# TSOC_PSoC4L.net
KiCad netlist of a schematic drawn in EAGLE
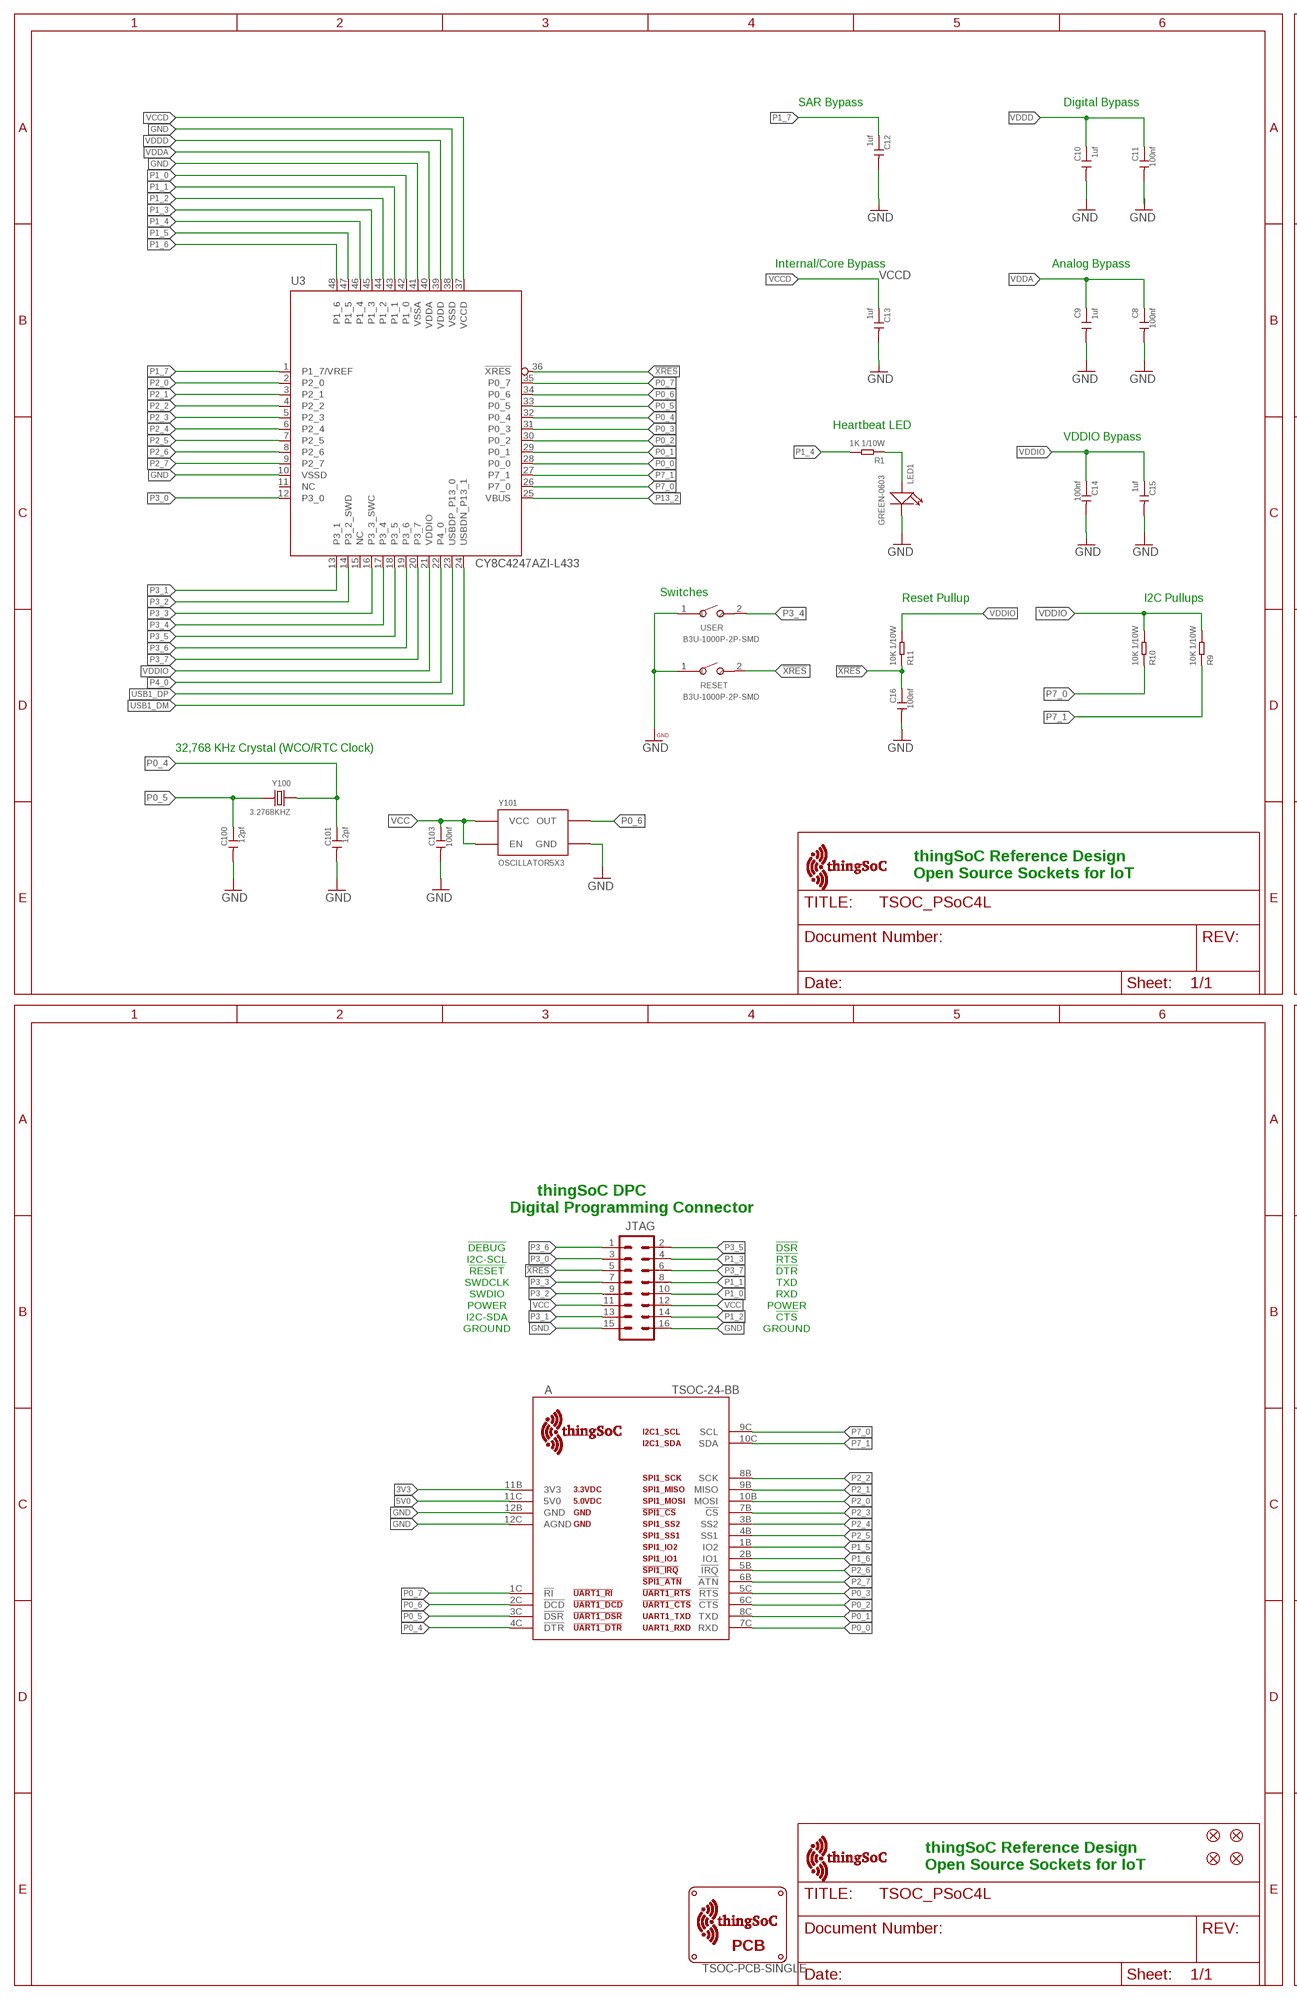
[diagram p0: schematic, sheet 1, part 1 of 2]
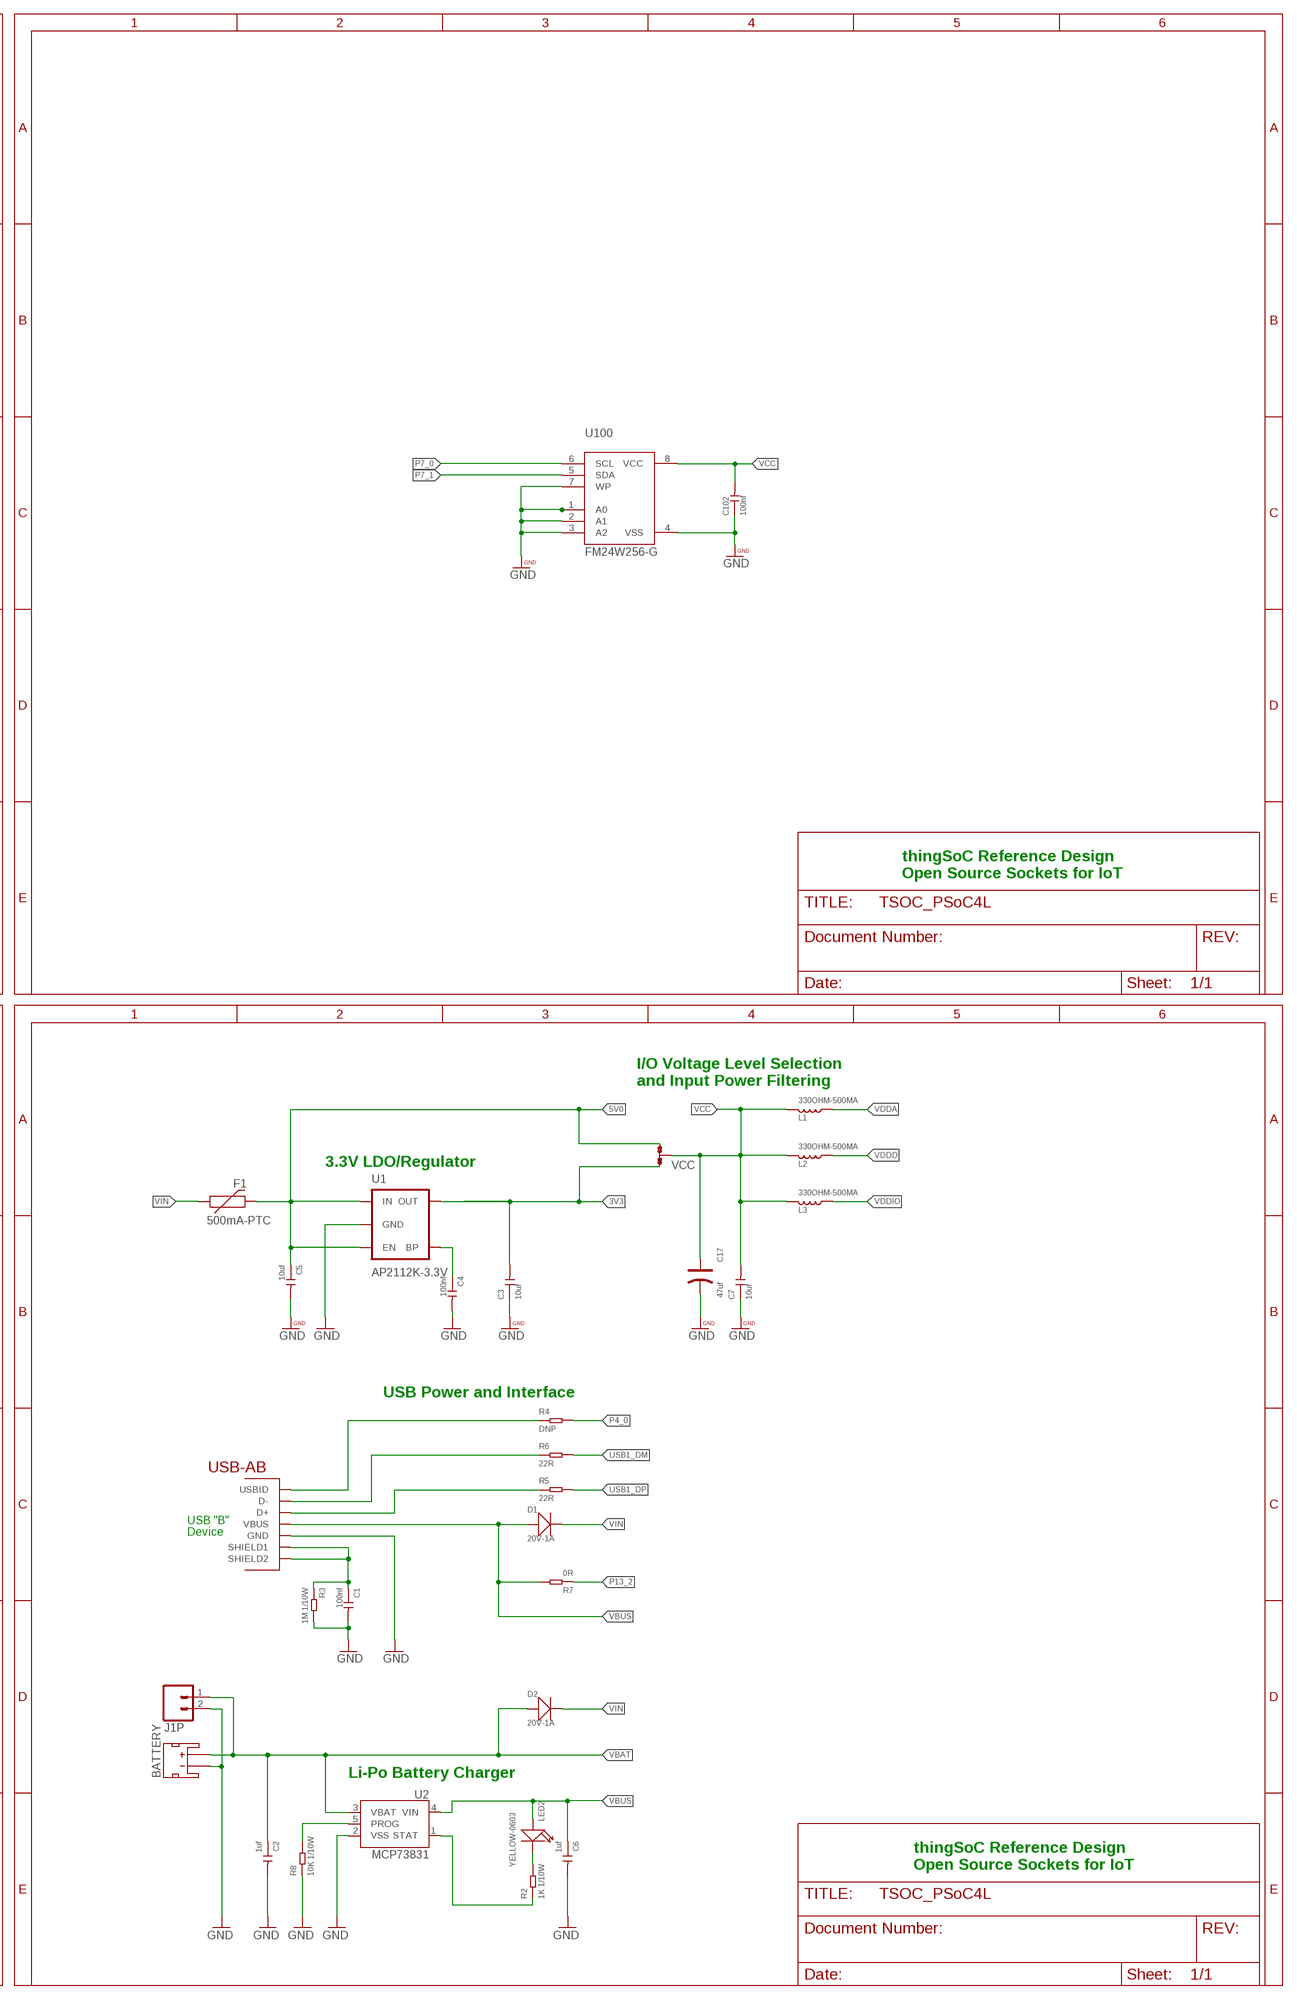
[diagram p1: schematic, sheet 1, part 2 of 2]

(export (version "E")
  (design (tool "Eeschema 10.0.6"))
  (components
    (comp (ref "A")
      (value "TSOC-24-BB")
      (footprint "eagle-import:TSOC-BB-S24")
      (libsource (lib "eagle-import") (part "TSOC-24-BB"))
    )
    (comp (ref "BATTERY")
      (value "JST_2MM_MALE")
      (footprint "eagle-import:JST-2-SMD")
      (libsource (lib "eagle-import") (part "JST_2MM_MALE"))
    )
    (comp (ref "C1")
      (value "100nf")
      (footprint "eagle-import:C0603")
      (fields (field (name "MPN") "CC0603KRX7R9BB104"))
      (libsource (lib "eagle-import") (part "CERAMIC-100NF-50V-10%-X7R(0603)"))
    )
    (comp (ref "C2")
      (value "1uf")
      (footprint "eagle-import:C0603")
      (fields (field (name "MPN") "CC0603KRX7R8BB105"))
      (libsource (lib "eagle-import") (part "CERAMIC-1UF-25V-10%-X7R(0603)"))
    )
    (comp (ref "C3")
      (value "10uf")
      (footprint "eagle-import:C0603")
      (fields (field (name "MPN") "CC0603KRX5R6BB106"))
      (libsource (lib "eagle-import") (part "CERAMIC-10UF-10V-10%-X5R(0603)"))
    )
    (comp (ref "C4")
      (value "100nf")
      (footprint "eagle-import:C0603")
      (fields (field (name "MPN") "CC0603KRX7R9BB104"))
      (libsource (lib "eagle-import") (part "CERAMIC-100NF-50V-10%-X7R(0603)"))
    )
    (comp (ref "C5")
      (value "10uf")
      (footprint "eagle-import:C0603")
      (fields (field (name "MPN") "CC0603KRX5R6BB106"))
      (libsource (lib "eagle-import") (part "CERAMIC-10UF-10V-10%-X5R(0603)"))
    )
    (comp (ref "C6")
      (value "1uf")
      (footprint "eagle-import:C0603")
      (fields (field (name "MPN") "CC0603KRX7R8BB105"))
      (libsource (lib "eagle-import") (part "CERAMIC-1UF-25V-10%-X7R(0603)"))
    )
    (comp (ref "C7")
      (value "10uf")
      (footprint "eagle-import:C0603")
      (fields (field (name "MPN") "CC0603KRX5R6BB106"))
      (libsource (lib "eagle-import") (part "CERAMIC-10UF-10V-10%-X5R(0603)"))
    )
    (comp (ref "C8")
      (value "100nf")
      (footprint "eagle-import:C0603")
      (fields (field (name "MPN") "CC0603KRX7R9BB104"))
      (libsource (lib "eagle-import") (part "CERAMIC-100NF-50V-10%-X7R(0603)"))
    )
    (comp (ref "C9")
      (value "1uf")
      (footprint "eagle-import:C0603")
      (fields (field (name "MPN") "CC0603KRX7R8BB105"))
      (libsource (lib "eagle-import") (part "CERAMIC-1UF-25V-10%-X7R(0603)"))
    )
    (comp (ref "C10")
      (value "1uf")
      (footprint "eagle-import:C0603")
      (fields (field (name "MPN") "CC0603KRX7R8BB105"))
      (libsource (lib "eagle-import") (part "CERAMIC-1UF-25V-10%-X7R(0603)"))
    )
    (comp (ref "C11")
      (value "100nf")
      (footprint "eagle-import:C0603")
      (fields (field (name "MPN") "CC0603KRX7R9BB104"))
      (libsource (lib "eagle-import") (part "CERAMIC-100NF-50V-10%-X7R(0603)"))
    )
    (comp (ref "C12")
      (value "1uf")
      (footprint "eagle-import:C0603")
      (fields (field (name "MPN") "CC0603KRX7R8BB105"))
      (libsource (lib "eagle-import") (part "CERAMIC-1UF-25V-10%-X7R(0603)"))
    )
    (comp (ref "C13")
      (value "1uf")
      (footprint "eagle-import:C0603")
      (fields (field (name "MPN") "CC0603KRX7R8BB105"))
      (libsource (lib "eagle-import") (part "CERAMIC-1UF-25V-10%-X7R(0603)"))
    )
    (comp (ref "C14")
      (value "100nf")
      (footprint "eagle-import:C0603")
      (fields (field (name "MPN") "CC0603KRX7R9BB104"))
      (libsource (lib "eagle-import") (part "CERAMIC-100NF-50V-10%-X7R(0603)"))
    )
    (comp (ref "C15")
      (value "1uf")
      (footprint "eagle-import:C0603")
      (fields (field (name "MPN") "CC0603KRX7R8BB105"))
      (libsource (lib "eagle-import") (part "CERAMIC-1UF-25V-10%-X7R(0603)"))
    )
    (comp (ref "C16")
      (value "100nf")
      (footprint "eagle-import:C0603")
      (fields (field (name "MPN") "CC0603KRX7R9BB104"))
      (libsource (lib "eagle-import") (part "CERAMIC-100NF-50V-10%-X7R(0603)"))
    )
    (comp (ref "C17")
      (value "47uf")
      (footprint "eagle-import:AVX-A")
      (fields (field (name "MPN") "TAJA476*006#NJ"))
      (libsource (lib "eagle-import") (part "TANTALUM-SMD-47UF-6.3V(AVX-A)"))
    )
    (comp (ref "C100")
      (value "12pf")
      (footprint "eagle-import:C0603")
      (fields (field (name "MPN") "CC0603JRNPO9BN120"))
      (libsource (lib "eagle-import") (part "CERAMIC-12PF-50V-5%-NPO(0603)"))
    )
    (comp (ref "C101")
      (value "12pf")
      (footprint "eagle-import:C0603")
      (fields (field (name "MPN") "CC0603JRNPO9BN120"))
      (libsource (lib "eagle-import") (part "CERAMIC-12PF-50V-5%-NPO(0603)"))
    )
    (comp (ref "C102")
      (value "100nf")
      (footprint "eagle-import:C0603")
      (fields (field (name "MPN") "CC0603KRX7R9BB104"))
      (libsource (lib "eagle-import") (part "CERAMIC-100NF-50V-10%-X7R(0603)"))
    )
    (comp (ref "C103")
      (value "100nf")
      (footprint "eagle-import:C0603")
      (fields (field (name "MPN") "CC0603KRX7R9BB104"))
      (libsource (lib "eagle-import") (part "CERAMIC-100NF-50V-10%-X7R(0603)"))
    )
    (comp (ref "D1")
      (value "20V-1A")
      (footprint "eagle-import:SOD-123")
      (fields (field (name "MPN") "B5819W"))
      (libsource (lib "eagle-import") (part "SMD-DIODE-SCHOTTKY-20V-1A(SOD-123)"))
    )
    (comp (ref "D2")
      (value "20V-1A")
      (footprint "eagle-import:SOD-123")
      (fields (field (name "MPN") "B5819W"))
      (libsource (lib "eagle-import") (part "SMD-DIODE-SCHOTTKY-20V-1A(SOD-123)"))
    )
    (comp (ref "F1")
      (value "500mA-PTC")
      (footprint "eagle-import:PTC-1206")
      (libsource (lib "eagle-import") (part "PTCSMD"))
    )
    (comp (ref "FID1")
      (value "FIDUCIALUFIDUCIAL")
      (footprint "eagle-import:MICRO-FIDUCIAL")
      (libsource (lib "eagle-import") (part "FIDUCIALUFIDUCIAL"))
    )
    (comp (ref "FID2")
      (value "FIDUCIALUFIDUCIAL")
      (footprint "eagle-import:MICRO-FIDUCIAL")
      (libsource (lib "eagle-import") (part "FIDUCIALUFIDUCIAL"))
    )
    (comp (ref "FID3")
      (value "FIDUCIALUFIDUCIAL")
      (footprint "eagle-import:MICRO-FIDUCIAL")
      (libsource (lib "eagle-import") (part "FIDUCIALUFIDUCIAL"))
    )
    (comp (ref "FID4")
      (value "FIDUCIALUFIDUCIAL")
      (footprint "eagle-import:MICRO-FIDUCIAL")
      (libsource (lib "eagle-import") (part "FIDUCIALUFIDUCIAL"))
    )
    (comp (ref "J1P")
      (value "M02-JST-2-PTH-NO_SILK")
      (footprint "eagle-import:JST-2-PTH-NS")
      (libsource (lib "eagle-import") (part "M02-JST-2-PTH-NO_SILK"))
    )
    (comp (ref "JTAG")
      (value "M08X2")
      (footprint "eagle-import:2X8")
      (libsource (lib "eagle-import") (part "M08X2"))
    )
    (comp (ref "L1")
      (value "330OHM-500MA")
      (footprint "eagle-import:L0603")
      (fields (field (name "MPN") "BLM18AG121SN1D"))
      (libsource (lib "eagle-import") (part "SMD-FERRITE-CHIP-120-OHM-500MA(0603)"))
    )
    (comp (ref "L2")
      (value "330OHM-500MA")
      (footprint "eagle-import:L0603")
      (fields (field (name "MPN") "BLM18AG121SN1D"))
      (libsource (lib "eagle-import") (part "SMD-FERRITE-CHIP-120-OHM-500MA(0603)"))
    )
    (comp (ref "L3")
      (value "330OHM-500MA")
      (footprint "eagle-import:L0603")
      (fields (field (name "MPN") "BLM18AG121SN1D"))
      (libsource (lib "eagle-import") (part "SMD-FERRITE-CHIP-120-OHM-500MA(0603)"))
    )
    (comp (ref "LED1")
      (value "GREEN-0603")
      (footprint "eagle-import:LED-0603")
      (fields (field (name "MPN") "19-217-G7C-AN1P2-3T"))
      (libsource (lib "eagle-import") (part "SMD-LED-CLEAR-GREEN(0603)"))
    )
    (comp (ref "LED2")
      (value "YELLOW-0603")
      (footprint "eagle-import:LED-0603")
      (fields (field (name "MPN") "19-217-Y5C-AM1N1VY-3T"))
      (libsource (lib "eagle-import") (part "SMD-LED-CLEAR-YELLOW(0603)"))
    )
    (comp (ref "R1")
      (value "1K 1/10W")
      (footprint "eagle-import:R0603")
      (fields (field (name "MPN") "RC0603JR-071KL"))
      (libsource (lib "eagle-import") (part "SMD-RES-1K-5%-1/10W(0603)"))
    )
    (comp (ref "R2")
      (value "1K 1/10W")
      (footprint "eagle-import:R0603")
      (fields (field (name "MPN") "RC0603JR-071KL"))
      (libsource (lib "eagle-import") (part "SMD-RES-1K-5%-1/10W(0603)"))
    )
    (comp (ref "R3")
      (value "1M 1/10W")
      (footprint "eagle-import:R0603")
      (fields (field (name "MPN") "RC0603JR-071ML"))
      (libsource (lib "eagle-import") (part "SMD-RES-1M-5%-1/10W(0603)"))
    )
    (comp (ref "R4")
      (value "DNP")
      (footprint "eagle-import:R0603")
      (fields (field (name "MPN") "RC0603JR-0722RL"))
      (libsource (lib "eagle-import") (part "SMD-RES-22R-5%-1/10W(0603)"))
    )
    (comp (ref "R5")
      (value "22R")
      (footprint "eagle-import:R0603")
      (fields (field (name "MPN") "RC0603JR-0722RL"))
      (libsource (lib "eagle-import") (part "SMD-RES-22R-5%-1/10W(0603)"))
    )
    (comp (ref "R6")
      (value "22R")
      (footprint "eagle-import:R0603")
      (fields (field (name "MPN") "RC0603JR-0722RL"))
      (libsource (lib "eagle-import") (part "SMD-RES-22R-5%-1/10W(0603)"))
    )
    (comp (ref "R7")
      (value "0R")
      (footprint "eagle-import:R0603")
      (fields (field (name "MPN") "RC0603JR-070RL"))
      (libsource (lib "eagle-import") (part "SMD-RES-0R-5%-1/10W(0603)"))
    )
    (comp (ref "R8")
      (value "10K 1/10W")
      (footprint "eagle-import:R0603")
      (fields (field (name "MPN") "RC0603JR-0710KL"))
      (libsource (lib "eagle-import") (part "SMD-RES-10K-5%-1/10W(0603)"))
    )
    (comp (ref "R9")
      (value "10K 1/10W")
      (footprint "eagle-import:R0603")
      (fields (field (name "MPN") "RC0603JR-0710KL"))
      (libsource (lib "eagle-import") (part "SMD-RES-10K-5%-1/10W(0603)"))
    )
    (comp (ref "R10")
      (value "10K 1/10W")
      (footprint "eagle-import:R0603")
      (fields (field (name "MPN") "RC0603JR-0710KL"))
      (libsource (lib "eagle-import") (part "SMD-RES-10K-5%-1/10W(0603)"))
    )
    (comp (ref "R11")
      (value "10K 1/10W")
      (footprint "eagle-import:R0603")
      (fields (field (name "MPN") "RC0603JR-0710KL"))
      (libsource (lib "eagle-import") (part "SMD-RES-10K-5%-1/10W(0603)"))
    )
    (comp (ref "RESET")
      (value "B3U-1000P-2P-SMD")
      (footprint "eagle-import:SW2-2.6-3.0X2.5X1.2+0.4MM")
      (libsource (lib "eagle-import") (part "SMD-BUTTON(2P-3.0X2.5X1.2+0.4MM)-B3U-1000P-2P-SMD"))
    )
    (comp (ref "U$1")
      (value "TSOC-PCB-SINGLE")
      (footprint "eagle-import:TSOC-BB-BRD-DIM")
      (libsource (lib "eagle-import") (part "TSOC-PCB-SINGLE"))
    )
    (comp (ref "U$100")
      (value "TSOC-LOGO-LRG")
      (footprint "eagle-import:TSOC-LOGO-LRG")
      (libsource (lib "eagle-import") (part "TSOC-LOGO-LRG"))
    )
    (comp (ref "U$101")
      (value "TSOC-LOGO-SMALL")
      (footprint "eagle-import:TSOC-LOGO-SML")
      (libsource (lib "eagle-import") (part "TSOC-LOGO-SMALL"))
    )
    (comp (ref "U1")
      (value "AP2112K-3.3V")
      (footprint "eagle-import:SOT23-5")
      (libsource (lib "eagle-import") (part "V_REG_LDOSMD"))
    )
    (comp (ref "U2")
      (value "MCP73831")
      (footprint "eagle-import:SOT23-5")
      (libsource (lib "eagle-import") (part "MCP73831"))
    )
    (comp (ref "U3")
      (value "CY8C4247AZI-L433")
      (footprint "eagle-import:TQFP-7X7-48")
      (libsource (lib "eagle-import") (part "CY8C4247AZI-L433"))
    )
    (comp (ref "U100")
      (value "FM24W256-G")
      (footprint "eagle-import:SO08")
      (libsource (lib "eagle-import") (part "FM24W256-G"))
    )
    (comp (ref "USB")
      (value "USB_AB")
      (footprint "eagle-import:USB-AB-MICRO-SMD")
      (libsource (lib "eagle-import") (part "USB_AB"))
    )
    (comp (ref "USER")
      (value "B3U-1000P-2P-SMD")
      (footprint "eagle-import:SW2-2.6-3.0X2.5X1.2+0.4MM")
      (libsource (lib "eagle-import") (part "SMD-BUTTON(2P-3.0X2.5X1.2+0.4MM)-B3U-1000P-2P-SMD"))
    )
    (comp (ref "VCC")
      (value "JMP-3-1_2")
      (footprint "eagle-import:JMP-3-1_2")
      (libsource (lib "eagle-import") (part "JMP-3-1_2"))
    )
    (comp (ref "Y100")
      (value "3.2768KHZ")
      (footprint "eagle-import:X2-SMD-L2.0X1.2X0.55MM")
      (fields (field (name "MPN") "FC-12M"))
      (libsource (lib "eagle-import") (part "SMD-CRYSTAL-32.768KHZ-12.5PF-20PPM-90K(2P-L2.0X1.2MM)"))
    )
    (comp (ref "Y101")
      (value "OSCILLATOR5X3")
      (footprint "eagle-import:CRYSTAL-SMD-5X3")
      (libsource (lib "eagle-import") (part "OSCILLATOR5X3"))
    )
  )
  (nets
    (net (code "1") (name "/~{XRES}") (class "Default")
      (node (ref "C16") (pin "1") (pinfunction "1_1") (pintype "passive"))
      (node (ref "JTAG") (pin "5") (pinfunction "5_5") (pintype "passive"))
      (node (ref "R11") (pin "1") (pinfunction "1_1") (pintype "passive"))
      (node (ref "RESET") (pin "2") (pinfunction "2_2") (pintype "bidirectional"))
      (node (ref "U3") (pin "36") (pinfunction "~{XRES}_36") (pintype "bidirectional"))
    )
    (net (code "2") (name "3V3") (class "Default")
      (node (ref "A") (pin "11B") (pinfunction "3V3_11B") (pintype "bidirectional"))
      (node (ref "C3") (pin "2") (pinfunction "2_2") (pintype "passive"))
      (node (ref "U1") (pin "5") (pinfunction "OUT_5") (pintype "passive"))
      (node (ref "VCC") (pin "1") (pinfunction "1_1") (pintype "passive"))
    )
    (net (code "3") (name "5V0") (class "Default")
      (node (ref "A") (pin "11C") (pinfunction "5V0_11C") (pintype "bidirectional"))
      (node (ref "C5") (pin "1") (pinfunction "1_1") (pintype "passive"))
      (node (ref "F1") (pin "2") (pinfunction "2_2") (pintype "bidirectional"))
      (node (ref "U1") (pin "1") (pinfunction "IN_1") (pintype "input"))
      (node (ref "U1") (pin "3") (pinfunction "EN_3") (pintype "input"))
      (node (ref "VCC") (pin "3") (pinfunction "3_3") (pintype "passive"))
    )
    (net (code "4") (name "GND") (class "Default")
      (node (ref "A") (pin "12B") (pinfunction "GND_12B") (pintype "bidirectional"))
      (node (ref "A") (pin "12C") (pinfunction "AGND_12C") (pintype "bidirectional"))
      (node (ref "BATTERY") (pin "1") (pinfunction "-_1") (pintype "bidirectional"))
      (node (ref "C1") (pin "2") (pinfunction "2_2") (pintype "passive"))
      (node (ref "C10") (pin "2") (pinfunction "2_2") (pintype "passive"))
      (node (ref "C100") (pin "2") (pinfunction "2_2") (pintype "passive"))
      (node (ref "C101") (pin "2") (pinfunction "2_2") (pintype "passive"))
      (node (ref "C102") (pin "1") (pinfunction "1_1") (pintype "passive"))
      (node (ref "C103") (pin "2") (pinfunction "2_2") (pintype "passive"))
      (node (ref "C11") (pin "2") (pinfunction "2_2") (pintype "passive"))
      (node (ref "C12") (pin "2") (pinfunction "2_2") (pintype "passive"))
      (node (ref "C13") (pin "2") (pinfunction "2_2") (pintype "passive"))
      (node (ref "C14") (pin "2") (pinfunction "2_2") (pintype "passive"))
      (node (ref "C15") (pin "2") (pinfunction "2_2") (pintype "passive"))
      (node (ref "C16") (pin "2") (pinfunction "2_2") (pintype "passive"))
      (node (ref "C17") (pin "-") (pinfunction "-_-") (pintype "passive"))
      (node (ref "C2") (pin "2") (pinfunction "2_2") (pintype "passive"))
      (node (ref "C3") (pin "1") (pinfunction "1_1") (pintype "passive"))
      (node (ref "C4") (pin "2") (pinfunction "2_2") (pintype "passive"))
      (node (ref "C5") (pin "2") (pinfunction "2_2") (pintype "passive"))
      (node (ref "C6") (pin "2") (pinfunction "2_2") (pintype "passive"))
      (node (ref "C7") (pin "1") (pinfunction "1_1") (pintype "passive"))
      (node (ref "C8") (pin "2") (pinfunction "2_2") (pintype "passive"))
      (node (ref "C9") (pin "2") (pinfunction "2_2") (pintype "passive"))
      (node (ref "J1P") (pin "2") (pinfunction "2_2") (pintype "passive"))
      (node (ref "JTAG") (pin "15") (pinfunction "15_15") (pintype "passive"))
      (node (ref "JTAG") (pin "16") (pinfunction "16_16") (pintype "passive"))
      (node (ref "LED1") (pin "-") (pinfunction "-_-") (pintype "passive"))
      (node (ref "R3") (pin "2") (pinfunction "2_2") (pintype "passive"))
      (node (ref "R8") (pin "1") (pinfunction "1_1") (pintype "passive"))
      (node (ref "RESET") (pin "1") (pinfunction "1_1") (pintype "bidirectional"))
      (node (ref "U1") (pin "2") (pinfunction "GND_2") (pintype "input"))
      (node (ref "U100") (pin "1") (pinfunction "A0_1") (pintype "bidirectional"))
      (node (ref "U100") (pin "2") (pinfunction "A1_2") (pintype "bidirectional"))
      (node (ref "U100") (pin "3") (pinfunction "A2_3") (pintype "bidirectional"))
      (node (ref "U100") (pin "4") (pinfunction "VSS_4") (pintype "power_in"))
      (node (ref "U100") (pin "7") (pinfunction "WP_7") (pintype "bidirectional"))
      (node (ref "U2") (pin "2") (pinfunction "VSS_2") (pintype "power_in"))
      (node (ref "U3") (pin "10") (pinfunction "VSSD_10") (pintype "bidirectional"))
      (node (ref "U3") (pin "38") (pinfunction "VSSD_38") (pintype "bidirectional"))
      (node (ref "U3") (pin "41") (pinfunction "VSSA_41") (pintype "bidirectional"))
      (node (ref "USB") (pin "GND") (pinfunction "GND_GND") (pintype "bidirectional"))
      (node (ref "USER") (pin "1") (pinfunction "1_1") (pintype "bidirectional"))
      (node (ref "Y101") (pin "2") (pinfunction "GND_2") (pintype "bidirectional"))
    )
    (net (code "5") (name "Net-(C1-Pad1)") (class "Default")
      (node (ref "C1") (pin "1") (pinfunction "1_1") (pintype "passive"))
      (node (ref "R3") (pin "1") (pinfunction "1_1") (pintype "passive"))
      (node (ref "USB") (pin "SHIELD1") (pinfunction "SHIELD1_SHIELD1") (pintype "bidirectional"))
      (node (ref "USB") (pin "SHIELD2") (pinfunction "SHIELD2_SHIELD2") (pintype "bidirectional"))
    )
    (net (code "6") (name "Net-(LED1-Pad+)") (class "Default")
      (node (ref "LED1") (pin "+") (pinfunction "+_+") (pintype "passive"))
      (node (ref "R1") (pin "1") (pinfunction "1_1") (pintype "passive"))
    )
    (net (code "7") (name "Net-(LED2-Pad-)") (class "Default")
      (node (ref "LED2") (pin "-") (pinfunction "-_-") (pintype "passive"))
      (node (ref "R2") (pin "2") (pinfunction "2_2") (pintype "passive"))
    )
    (net (code "8") (name "Net-(R5-Pad1)") (class "Default")
      (node (ref "R5") (pin "1") (pinfunction "1_1") (pintype "passive"))
      (node (ref "USB") (pin "D+") (pinfunction "D+_D+") (pintype "bidirectional"))
    )
    (net (code "9") (name "Net-(R6-Pad1)") (class "Default")
      (node (ref "R6") (pin "1") (pinfunction "1_1") (pintype "passive"))
      (node (ref "USB") (pin "D-") (pinfunction "D-_D-") (pintype "bidirectional"))
    )
    (net (code "10") (name "Net-(U1-BP)") (class "Default")
      (node (ref "C4") (pin "1") (pinfunction "1_1") (pintype "passive"))
      (node (ref "U1") (pin "4") (pinfunction "BP_4") (pintype "input"))
    )
    (net (code "11") (name "Net-(U2-PROG)") (class "Default")
      (node (ref "R8") (pin "2") (pinfunction "2_2") (pintype "passive"))
      (node (ref "U2") (pin "5") (pinfunction "PROG_5") (pintype "input"))
    )
    (net (code "12") (name "Net-(U2-STAT)") (class "Default")
      (node (ref "R2") (pin "1") (pinfunction "1_1") (pintype "passive"))
      (node (ref "U2") (pin "1") (pinfunction "STAT_1") (pintype "output"))
    )
    (net (code "13") (name "Net-(USB-USBID)") (class "Default")
      (node (ref "R4") (pin "1") (pinfunction "1_1") (pintype "passive"))
      (node (ref "USB") (pin "ID") (pinfunction "USBID_ID") (pintype "bidirectional"))
    )
    (net (code "14") (name "P0_0") (class "Default")
      (node (ref "A") (pin "7C") (pinfunction "RXD_7C") (pintype "bidirectional"))
      (node (ref "U3") (pin "28") (pinfunction "P0_0_28") (pintype "bidirectional"))
    )
    (net (code "15") (name "P0_1") (class "Default")
      (node (ref "A") (pin "8C") (pinfunction "TXD_8C") (pintype "bidirectional"))
      (node (ref "U3") (pin "29") (pinfunction "P0_1_29") (pintype "bidirectional"))
    )
    (net (code "16") (name "P0_2") (class "Default")
      (node (ref "A") (pin "6C") (pinfunction "~{CTS}_6C") (pintype "bidirectional"))
      (node (ref "U3") (pin "30") (pinfunction "P0_2_30") (pintype "input"))
    )
    (net (code "17") (name "P0_3") (class "Default")
      (node (ref "A") (pin "5C") (pinfunction "~{RTS}_5C") (pintype "bidirectional"))
      (node (ref "U3") (pin "31") (pinfunction "P0_3_31") (pintype "bidirectional"))
    )
    (net (code "18") (name "P0_4") (class "Default")
      (node (ref "A") (pin "4C") (pinfunction "~{DTR}_4C") (pintype "bidirectional"))
      (node (ref "C101") (pin "1") (pinfunction "1_1") (pintype "passive"))
      (node (ref "U3") (pin "32") (pinfunction "P0_4_32") (pintype "bidirectional"))
      (node (ref "Y100") (pin "1") (pinfunction "1_1") (pintype "passive"))
    )
    (net (code "19") (name "P0_5") (class "Default")
      (node (ref "A") (pin "3C") (pinfunction "~{DSR}_3C") (pintype "bidirectional"))
      (node (ref "C100") (pin "1") (pinfunction "1_1") (pintype "passive"))
      (node (ref "U3") (pin "33") (pinfunction "P0_5_33") (pintype "bidirectional"))
      (node (ref "Y100") (pin "2") (pinfunction "2_2") (pintype "passive"))
    )
    (net (code "20") (name "P0_6") (class "Default")
      (node (ref "A") (pin "2C") (pinfunction "~{DCD}_2C") (pintype "bidirectional"))
      (node (ref "U3") (pin "34") (pinfunction "P0_6_34") (pintype "power_in"))
      (node (ref "Y101") (pin "3") (pinfunction "OUT_3") (pintype "bidirectional"))
    )
    (net (code "21") (name "P0_7") (class "Default")
      (node (ref "A") (pin "1C") (pinfunction "~{RI}_1C") (pintype "bidirectional"))
      (node (ref "U3") (pin "35") (pinfunction "P0_7_35") (pintype "bidirectional"))
    )
    (net (code "22") (name "P1_0") (class "Default")
      (node (ref "JTAG") (pin "10") (pinfunction "10_10") (pintype "passive"))
      (node (ref "U3") (pin "42") (pinfunction "P1_0_42") (pintype "bidirectional"))
    )
    (net (code "23") (name "P1_1") (class "Default")
      (node (ref "JTAG") (pin "8") (pinfunction "8_8") (pintype "passive"))
      (node (ref "U3") (pin "43") (pinfunction "P1_1_43") (pintype "bidirectional"))
    )
    (net (code "24") (name "P1_2") (class "Default")
      (node (ref "JTAG") (pin "14") (pinfunction "14_14") (pintype "passive"))
      (node (ref "U3") (pin "44") (pinfunction "P1_2_44") (pintype "power_in"))
    )
    (net (code "25") (name "P1_3") (class "Default")
      (node (ref "JTAG") (pin "4") (pinfunction "4_4") (pintype "passive"))
      (node (ref "U3") (pin "45") (pinfunction "P1_3_45") (pintype "bidirectional"))
    )
    (net (code "26") (name "P1_4") (class "Default")
      (node (ref "R1") (pin "2") (pinfunction "2_2") (pintype "passive"))
      (node (ref "U3") (pin "46") (pinfunction "P1_4_46") (pintype "bidirectional"))
    )
    (net (code "27") (name "P1_5") (class "Default")
      (node (ref "A") (pin "1B") (pinfunction "IO2_1B") (pintype "bidirectional"))
      (node (ref "U3") (pin "47") (pinfunction "P1_5_47") (pintype "bidirectional"))
    )
    (net (code "28") (name "P1_6") (class "Default")
      (node (ref "A") (pin "2B") (pinfunction "IO1_2B") (pintype "bidirectional"))
      (node (ref "U3") (pin "48") (pinfunction "P1_6_48") (pintype "bidirectional"))
    )
    (net (code "29") (name "P1_7") (class "Default")
      (node (ref "C12") (pin "1") (pinfunction "1_1") (pintype "passive"))
      (node (ref "U3") (pin "1") (pinfunction "P1_7/VREF_1") (pintype "bidirectional"))
    )
    (net (code "30") (name "P2_0") (class "Default")
      (node (ref "A") (pin "10B") (pinfunction "MOSI_10B") (pintype "bidirectional"))
      (node (ref "U3") (pin "2") (pinfunction "P2_0_2") (pintype "bidirectional"))
    )
    (net (code "31") (name "P2_1") (class "Default")
      (node (ref "A") (pin "9B") (pinfunction "MISO_9B") (pintype "bidirectional"))
      (node (ref "U3") (pin "3") (pinfunction "P2_1_3") (pintype "bidirectional"))
    )
    (net (code "32") (name "P2_2") (class "Default")
      (node (ref "A") (pin "8B") (pinfunction "SCK_8B") (pintype "bidirectional"))
      (node (ref "U3") (pin "4") (pinfunction "P2_2_4") (pintype "power_in"))
    )
    (net (code "33") (name "P2_3") (class "Default")
      (node (ref "A") (pin "7B") (pinfunction "~{CS}_7B") (pintype "bidirectional"))
      (node (ref "U3") (pin "5") (pinfunction "P2_3_5") (pintype "bidirectional"))
    )
    (net (code "34") (name "P2_4") (class "Default")
      (node (ref "A") (pin "3B") (pinfunction "SS2_3B") (pintype "bidirectional"))
      (node (ref "U3") (pin "6") (pinfunction "P2_4_6") (pintype "bidirectional"))
    )
    (net (code "35") (name "P2_5") (class "Default")
      (node (ref "A") (pin "4B") (pinfunction "SS1_4B") (pintype "bidirectional"))
      (node (ref "U3") (pin "7") (pinfunction "P2_5_7") (pintype "bidirectional"))
    )
    (net (code "36") (name "P2_6") (class "Default")
      (node (ref "A") (pin "5B") (pinfunction "~{IRQ}_5B") (pintype "bidirectional"))
      (node (ref "U3") (pin "8") (pinfunction "P2_6_8") (pintype "power_in"))
    )
    (net (code "37") (name "P2_7") (class "Default")
      (node (ref "A") (pin "6B") (pinfunction "~{ATN}_6B") (pintype "bidirectional"))
      (node (ref "U3") (pin "9") (pinfunction "P2_7_9") (pintype "bidirectional"))
    )
    (net (code "38") (name "P3_0") (class "Default")
      (node (ref "JTAG") (pin "3") (pinfunction "3_3") (pintype "passive"))
      (node (ref "U3") (pin "12") (pinfunction "P3_0_12") (pintype "bidirectional"))
    )
    (net (code "39") (name "P3_1") (class "Default")
      (node (ref "JTAG") (pin "13") (pinfunction "13_13") (pintype "passive"))
      (node (ref "U3") (pin "13") (pinfunction "P3_1_13") (pintype "bidirectional"))
    )
    (net (code "40") (name "P3_2") (class "Default")
      (node (ref "JTAG") (pin "9") (pinfunction "9_9") (pintype "passive"))
      (node (ref "U3") (pin "14") (pinfunction "P3_2_SWD_14") (pintype "bidirectional"))
    )
    (net (code "41") (name "P3_3") (class "Default")
      (node (ref "JTAG") (pin "7") (pinfunction "7_7") (pintype "passive"))
      (node (ref "U3") (pin "16") (pinfunction "P3_3_SWC_16") (pintype "bidirectional"))
    )
    (net (code "42") (name "P3_4") (class "Default")
      (node (ref "U3") (pin "17") (pinfunction "P3_4_17") (pintype "bidirectional"))
      (node (ref "USER") (pin "2") (pinfunction "2_2") (pintype "bidirectional"))
    )
    (net (code "43") (name "P3_5") (class "Default")
      (node (ref "JTAG") (pin "2") (pinfunction "2_2") (pintype "passive"))
      (node (ref "U3") (pin "18") (pinfunction "P3_5_18") (pintype "bidirectional"))
    )
    (net (code "44") (name "P3_6") (class "Default")
      (node (ref "JTAG") (pin "1") (pinfunction "1_1") (pintype "passive"))
      (node (ref "U3") (pin "19") (pinfunction "P3_6_19") (pintype "power_in"))
    )
    (net (code "45") (name "P3_7") (class "Default")
      (node (ref "JTAG") (pin "6") (pinfunction "6_6") (pintype "passive"))
      (node (ref "U3") (pin "20") (pinfunction "P3_7_20") (pintype "bidirectional"))
    )
    (net (code "46") (name "P4_0") (class "Default")
      (node (ref "R4") (pin "2") (pinfunction "2_2") (pintype "passive"))
      (node (ref "U3") (pin "22") (pinfunction "P4_0_22") (pintype "bidirectional"))
    )
    (net (code "47") (name "P7_0") (class "Default")
      (node (ref "A") (pin "9C") (pinfunction "SCL_9C") (pintype "bidirectional"))
      (node (ref "R10") (pin "1") (pinfunction "1_1") (pintype "passive"))
      (node (ref "U100") (pin "6") (pinfunction "SCL_6") (pintype "bidirectional"))
      (node (ref "U3") (pin "26") (pinfunction "P7_0_26") (pintype "bidirectional"))
    )
    (net (code "48") (name "P7_1") (class "Default")
      (node (ref "A") (pin "10C") (pinfunction "SDA_10C") (pintype "bidirectional"))
      (node (ref "R9") (pin "1") (pinfunction "1_1") (pintype "passive"))
      (node (ref "U100") (pin "5") (pinfunction "SDA_5") (pintype "bidirectional"))
      (node (ref "U3") (pin "27") (pinfunction "P7_1_27") (pintype "bidirectional"))
    )
    (net (code "49") (name "P13_2") (class "Default")
      (node (ref "R7") (pin "1") (pinfunction "1_1") (pintype "passive"))
      (node (ref "U3") (pin "25") (pinfunction "VBUS_25") (pintype "bidirectional"))
    )
    (net (code "50") (name "USB1_DM") (class "Default")
      (node (ref "R6") (pin "2") (pinfunction "2_2") (pintype "passive"))
      (node (ref "U3") (pin "24") (pinfunction "USBDN_P13_1_24") (pintype "bidirectional"))
    )
    (net (code "51") (name "USB1_DP") (class "Default")
      (node (ref "R5") (pin "2") (pinfunction "2_2") (pintype "passive"))
      (node (ref "U3") (pin "23") (pinfunction "USBDP_P13_0_23") (pintype "bidirectional"))
    )
    (net (code "52") (name "VBAT") (class "Default")
      (node (ref "BATTERY") (pin "2") (pinfunction "+_2") (pintype "bidirectional"))
      (node (ref "C2") (pin "1") (pinfunction "1_1") (pintype "passive"))
      (node (ref "D2") (pin "+") (pinfunction "+_+") (pintype "passive"))
      (node (ref "J1P") (pin "1") (pinfunction "1_1") (pintype "passive"))
      (node (ref "U2") (pin "3") (pinfunction "VBAT_3") (pintype "power_in"))
    )
    (net (code "53") (name "VBUS") (class "Default")
      (node (ref "C6") (pin "1") (pinfunction "1_1") (pintype "passive"))
      (node (ref "D1") (pin "+") (pinfunction "+_+") (pintype "passive"))
      (node (ref "LED2") (pin "+") (pinfunction "+_+") (pintype "passive"))
      (node (ref "R7") (pin "2") (pinfunction "2_2") (pintype "passive"))
      (node (ref "U2") (pin "4") (pinfunction "VIN_4") (pintype "power_in"))
      (node (ref "USB") (pin "VBUS") (pinfunction "VBUS_VBUS") (pintype "bidirectional"))
    )
    (net (code "54") (name "VCC") (class "Default")
      (node (ref "C102") (pin "2") (pinfunction "2_2") (pintype "passive"))
      (node (ref "C103") (pin "1") (pinfunction "1_1") (pintype "passive"))
      (node (ref "C17") (pin "+") (pinfunction "+_+") (pintype "passive"))
      (node (ref "C7") (pin "2") (pinfunction "2_2") (pintype "passive"))
      (node (ref "JTAG") (pin "11") (pinfunction "11_11") (pintype "passive"))
      (node (ref "JTAG") (pin "12") (pinfunction "12_12") (pintype "passive"))
      (node (ref "L1") (pin "1") (pinfunction "1_1") (pintype "passive"))
      (node (ref "L2") (pin "1") (pinfunction "1_1") (pintype "passive"))
      (node (ref "L3") (pin "1") (pinfunction "1_1") (pintype "passive"))
      (node (ref "U100") (pin "8") (pinfunction "VCC_8") (pintype "power_in"))
      (node (ref "VCC") (pin "2") (pinfunction "2_2") (pintype "passive"))
      (node (ref "Y101") (pin "1") (pinfunction "EN_1") (pintype "bidirectional"))
      (node (ref "Y101") (pin "4") (pinfunction "VCC_4") (pintype "bidirectional"))
    )
    (net (code "55") (name "VCCD") (class "Default")
      (node (ref "C13") (pin "1") (pinfunction "1_1") (pintype "passive"))
      (node (ref "U3") (pin "37") (pinfunction "VCCD_37") (pintype "bidirectional"))
    )
    (net (code "56") (name "VDDA") (class "Default")
      (node (ref "C8") (pin "1") (pinfunction "1_1") (pintype "passive"))
      (node (ref "C9") (pin "1") (pinfunction "1_1") (pintype "passive"))
      (node (ref "L1") (pin "2") (pinfunction "2_2") (pintype "passive"))
      (node (ref "U3") (pin "40") (pinfunction "VDDA_40") (pintype "bidirectional"))
    )
    (net (code "57") (name "VDDD") (class "Default")
      (node (ref "C10") (pin "1") (pinfunction "1_1") (pintype "passive"))
      (node (ref "C11") (pin "1") (pinfunction "1_1") (pintype "passive"))
      (node (ref "L2") (pin "2") (pinfunction "2_2") (pintype "passive"))
      (node (ref "U3") (pin "39") (pinfunction "VDDD_39") (pintype "bidirectional"))
    )
    (net (code "58") (name "VDDIO") (class "Default")
      (node (ref "C14") (pin "1") (pinfunction "1_1") (pintype "passive"))
      (node (ref "C15") (pin "1") (pinfunction "1_1") (pintype "passive"))
      (node (ref "L3") (pin "2") (pinfunction "2_2") (pintype "passive"))
      (node (ref "R10") (pin "2") (pinfunction "2_2") (pintype "passive"))
      (node (ref "R11") (pin "2") (pinfunction "2_2") (pintype "passive"))
      (node (ref "R9") (pin "2") (pinfunction "2_2") (pintype "passive"))
      (node (ref "U3") (pin "21") (pinfunction "VDDIO_21") (pintype "bidirectional"))
    )
    (net (code "59") (name "VIN") (class "Default")
      (node (ref "D1") (pin "-") (pinfunction "-_-") (pintype "passive"))
      (node (ref "D2") (pin "-") (pinfunction "-_-") (pintype "passive"))
      (node (ref "F1") (pin "1") (pinfunction "1_1") (pintype "bidirectional"))
    )
    (net (code "60") (name "unconnected-(BATTERY-PAD1-PadNC1)") (class "Default")
      (node (ref "BATTERY") (pin "NC1") (pinfunction "PAD1_NC1") (pintype "bidirectional"))
    )
    (net (code "61") (name "unconnected-(BATTERY-PAD2-PadNC2)") (class "Default")
      (node (ref "BATTERY") (pin "NC2") (pinfunction "PAD2_NC2") (pintype "bidirectional"))
    )
    (net (code "62") (name "unconnected-(U3-NC-Pad11)") (class "Default")
      (node (ref "U3") (pin "11") (pinfunction "NC_11") (pintype "bidirectional"))
    )
    (net (code "63") (name "unconnected-(U3-NC-Pad15)") (class "Default")
      (node (ref "U3") (pin "15") (pinfunction "NC_15") (pintype "bidirectional"))
    )
  )
)
